# SCH__LM393_2022-09-28.net
KiCad netlist of a schematic drawn in EasyEDA
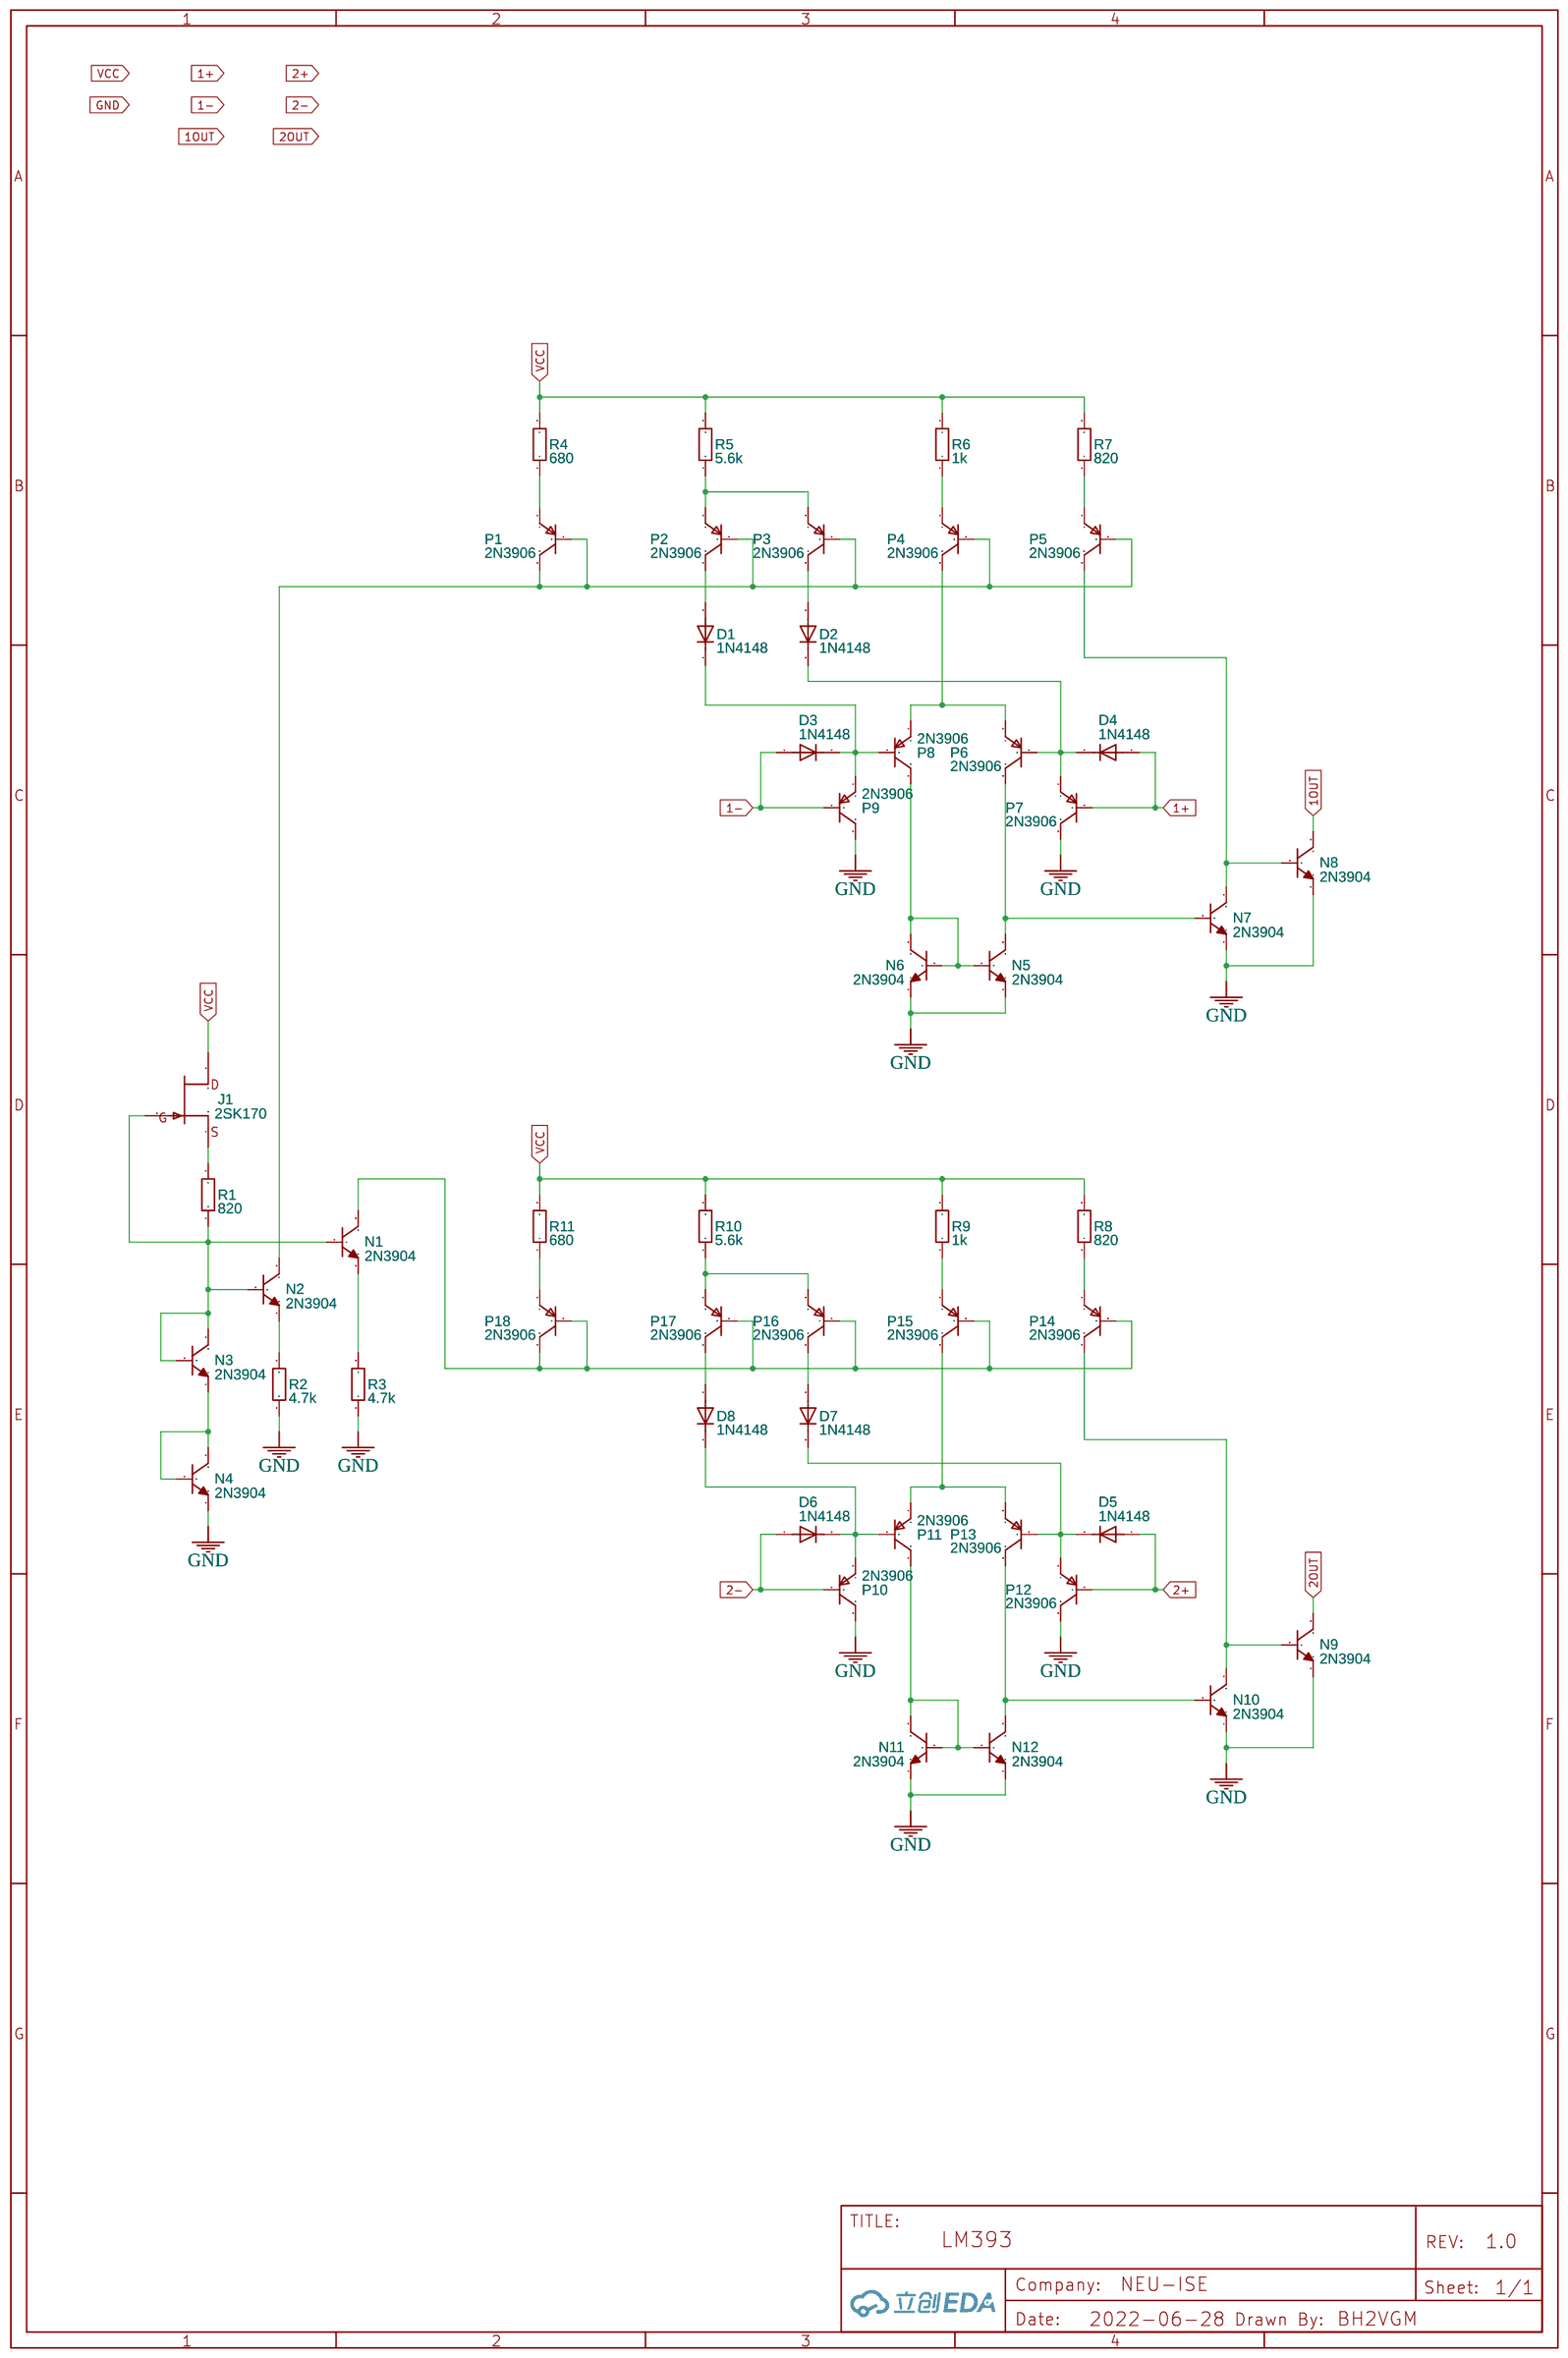
[diagram p0: schematic sheet]

(export (version "E")
  (design (tool "Eeschema 10.0.6"))
  (components
    (comp (ref "D1") (value "1N4148") (libsource (lib "") (part "1N4148 DO-35")))
    (comp (ref "D2") (value "1N4148") (libsource (lib "") (part "1N4148 DO-35")))
    (comp (ref "D3") (value "1N4148") (libsource (lib "") (part "1N4148 DO-35_1")))
    (comp (ref "D4") (value "1N4148") (libsource (lib "") (part "1N4148 DO-35_2")))
    (comp (ref "D5") (value "1N4148") (libsource (lib "") (part "1N4148 DO-35_2")))
    (comp (ref "D6") (value "1N4148") (libsource (lib "") (part "1N4148 DO-35_1")))
    (comp (ref "D7") (value "1N4148") (libsource (lib "") (part "1N4148 DO-35")))
    (comp (ref "D8") (value "1N4148") (libsource (lib "") (part "1N4148 DO-35")))
    (comp (ref "J1") (value "2SK170") (libsource (lib "") (part "2SK170")))
    (comp (ref "N1")
      (value "2N3904")
      (fields (field (name "BOM_Supplier Part") "C118538"))
      (libsource (lib "") (part "2N3904"))
    )
    (comp (ref "N2")
      (value "2N3904")
      (fields (field (name "BOM_Supplier Part") "C118538"))
      (libsource (lib "") (part "2N3904"))
    )
    (comp (ref "N3")
      (value "2N3904")
      (fields (field (name "BOM_Supplier Part") "C118538"))
      (libsource (lib "") (part "2N3904"))
    )
    (comp (ref "N4")
      (value "2N3904")
      (fields (field (name "BOM_Supplier Part") "C118538"))
      (libsource (lib "") (part "2N3904"))
    )
    (comp (ref "N5")
      (value "2N3904")
      (fields (field (name "BOM_Supplier Part") "C118538"))
      (libsource (lib "") (part "2N3904"))
    )
    (comp (ref "N6")
      (value "2N3904")
      (fields (field (name "BOM_Supplier Part") "C118538"))
      (libsource (lib "") (part "2N3904_1"))
    )
    (comp (ref "N7")
      (value "2N3904")
      (fields (field (name "BOM_Supplier Part") "C118538"))
      (libsource (lib "") (part "2N3904"))
    )
    (comp (ref "N8")
      (value "2N3904")
      (fields (field (name "BOM_Supplier Part") "C118538"))
      (libsource (lib "") (part "2N3904"))
    )
    (comp (ref "N9")
      (value "2N3904")
      (fields (field (name "BOM_Supplier Part") "C118538"))
      (libsource (lib "") (part "2N3904"))
    )
    (comp (ref "N10")
      (value "2N3904")
      (fields (field (name "BOM_Supplier Part") "C118538"))
      (libsource (lib "") (part "2N3904"))
    )
    (comp (ref "N11")
      (value "2N3904")
      (fields (field (name "BOM_Supplier Part") "C118538"))
      (libsource (lib "") (part "2N3904_1"))
    )
    (comp (ref "N12")
      (value "2N3904")
      (fields (field (name "BOM_Supplier Part") "C118538"))
      (libsource (lib "") (part "2N3904"))
    )
    (comp (ref "P1")
      (value "2N3906")
      (fields (field (name "BOM_Supplier Part") "C9809"))
      (libsource (lib "") (part "2N3906"))
    )
    (comp (ref "P2")
      (value "2N3906")
      (fields (field (name "BOM_Supplier Part") "C9809"))
      (libsource (lib "") (part "2N3906"))
    )
    (comp (ref "P3")
      (value "2N3906")
      (fields (field (name "BOM_Supplier Part") "C9809"))
      (libsource (lib "") (part "2N3906"))
    )
    (comp (ref "P4")
      (value "2N3906")
      (fields (field (name "BOM_Supplier Part") "C9809"))
      (libsource (lib "") (part "2N3906"))
    )
    (comp (ref "P5")
      (value "2N3906")
      (fields (field (name "BOM_Supplier Part") "C9809"))
      (libsource (lib "") (part "2N3906"))
    )
    (comp (ref "P6")
      (value "2N3906")
      (fields (field (name "BOM_Supplier Part") "C9809"))
      (libsource (lib "") (part "2N3906"))
    )
    (comp (ref "P7")
      (value "2N3906")
      (fields (field (name "BOM_Supplier Part") "C9809"))
      (libsource (lib "") (part "2N3906"))
    )
    (comp (ref "P8")
      (value "2N3906")
      (fields (field (name "BOM_Supplier Part") "C9809"))
      (libsource (lib "") (part "2N3906_1"))
    )
    (comp (ref "P9")
      (value "2N3906")
      (fields (field (name "BOM_Supplier Part") "C9809"))
      (libsource (lib "") (part "2N3906_1"))
    )
    (comp (ref "P10")
      (value "2N3906")
      (fields (field (name "BOM_Supplier Part") "C9809"))
      (libsource (lib "") (part "2N3906_1"))
    )
    (comp (ref "P11")
      (value "2N3906")
      (fields (field (name "BOM_Supplier Part") "C9809"))
      (libsource (lib "") (part "2N3906_1"))
    )
    (comp (ref "P12")
      (value "2N3906")
      (fields (field (name "BOM_Supplier Part") "C9809"))
      (libsource (lib "") (part "2N3906"))
    )
    (comp (ref "P13")
      (value "2N3906")
      (fields (field (name "BOM_Supplier Part") "C9809"))
      (libsource (lib "") (part "2N3906"))
    )
    (comp (ref "P14")
      (value "2N3906")
      (fields (field (name "BOM_Supplier Part") "C9809"))
      (libsource (lib "") (part "2N3906"))
    )
    (comp (ref "P15")
      (value "2N3906")
      (fields (field (name "BOM_Supplier Part") "C9809"))
      (libsource (lib "") (part "2N3906"))
    )
    (comp (ref "P16")
      (value "2N3906")
      (fields (field (name "BOM_Supplier Part") "C9809"))
      (libsource (lib "") (part "2N3906"))
    )
    (comp (ref "P17")
      (value "2N3906")
      (fields (field (name "BOM_Supplier Part") "C9809"))
      (libsource (lib "") (part "2N3906"))
    )
    (comp (ref "P18")
      (value "2N3906")
      (fields (field (name "BOM_Supplier Part") "C9809"))
      (libsource (lib "") (part "2N3906"))
    )
    (comp (ref "R1") (value "820") (libsource (lib "") (part "TR0805D220KP0550Z")))
    (comp (ref "R2") (value "4.7k") (libsource (lib "") (part "TR0805D220KP0550Z")))
    (comp (ref "R3") (value "4.7k") (libsource (lib "") (part "TR0805D220KP0550Z")))
    (comp (ref "R4") (value "680") (libsource (lib "") (part "TR0805D220KP0550Z")))
    (comp (ref "R5") (value "5.6k") (libsource (lib "") (part "TR0805D220KP0550Z")))
    (comp (ref "R6") (value "1k") (libsource (lib "") (part "TR0805D220KP0550Z")))
    (comp (ref "R7") (value "820") (libsource (lib "") (part "TR0805D220KP0550Z")))
    (comp (ref "R8") (value "820") (libsource (lib "") (part "TR0805D220KP0550Z")))
    (comp (ref "R9") (value "1k") (libsource (lib "") (part "TR0805D220KP0550Z")))
    (comp (ref "R10") (value "5.6k") (libsource (lib "") (part "TR0805D220KP0550Z")))
    (comp (ref "R11") (value "680") (libsource (lib "") (part "TR0805D220KP0550Z")))
  )
  (nets
    (net (code "1") (name "1+") (class "Default")
      (node (ref "D4") (pin "1") (pinfunction "1_1") (pintype "unspecified"))
      (node (ref "P7") (pin "2") (pinfunction "B_2") (pintype "unspecified"))
    )
    (net (code "2") (name "1-") (class "Default")
      (node (ref "D3") (pin "1") (pinfunction "1_1") (pintype "unspecified"))
      (node (ref "P9") (pin "2") (pinfunction "B_2") (pintype "unspecified"))
    )
    (net (code "3") (name "1OUT") (class "Default")
      (node (ref "N8") (pin "3") (pinfunction "C_3") (pintype "unspecified"))
    )
    (net (code "4") (name "2+") (class "Default")
      (node (ref "D5") (pin "1") (pinfunction "1_1") (pintype "unspecified"))
      (node (ref "P12") (pin "2") (pinfunction "B_2") (pintype "unspecified"))
    )
    (net (code "5") (name "2-") (class "Default")
      (node (ref "D6") (pin "1") (pinfunction "1_1") (pintype "unspecified"))
      (node (ref "P10") (pin "2") (pinfunction "B_2") (pintype "unspecified"))
    )
    (net (code "6") (name "2OUT") (class "Default")
      (node (ref "N9") (pin "3") (pinfunction "C_3") (pintype "unspecified"))
    )
    (net (code "7") (name "GND") (class "Default")
      (node (ref "N10") (pin "1") (pinfunction "E_1") (pintype "unspecified"))
      (node (ref "N11") (pin "1") (pinfunction "E_1") (pintype "unspecified"))
      (node (ref "N12") (pin "1") (pinfunction "E_1") (pintype "unspecified"))
      (node (ref "N4") (pin "1") (pinfunction "E_1") (pintype "unspecified"))
      (node (ref "N5") (pin "1") (pinfunction "E_1") (pintype "unspecified"))
      (node (ref "N6") (pin "1") (pinfunction "E_1") (pintype "unspecified"))
      (node (ref "N7") (pin "1") (pinfunction "E_1") (pintype "unspecified"))
      (node (ref "N8") (pin "1") (pinfunction "E_1") (pintype "unspecified"))
      (node (ref "N9") (pin "1") (pinfunction "E_1") (pintype "unspecified"))
      (node (ref "P10") (pin "3") (pinfunction "C_3") (pintype "unspecified"))
      (node (ref "P12") (pin "3") (pinfunction "C_3") (pintype "unspecified"))
      (node (ref "P7") (pin "3") (pinfunction "C_3") (pintype "unspecified"))
      (node (ref "P9") (pin "3") (pinfunction "C_3") (pintype "unspecified"))
      (node (ref "R2") (pin "1") (pinfunction "1_1") (pintype "input"))
      (node (ref "R3") (pin "1") (pinfunction "1_1") (pintype "input"))
    )
    (net (code "8") (name "Net-(J1-G)") (class "Default")
      (node (ref "J1") (pin "2") (pinfunction "G_2") (pintype "unspecified"))
      (node (ref "N1") (pin "2") (pinfunction "B_2") (pintype "unspecified"))
      (node (ref "N2") (pin "2") (pinfunction "B_2") (pintype "unspecified"))
      (node (ref "N3") (pin "2") (pinfunction "B_2") (pintype "unspecified"))
      (node (ref "N3") (pin "3") (pinfunction "C_3") (pintype "unspecified"))
      (node (ref "R1") (pin "1") (pinfunction "1_1") (pintype "input"))
    )
    (net (code "9") (name "Net-(J1-S)") (class "Default")
      (node (ref "J1") (pin "1") (pinfunction "S_1") (pintype "unspecified"))
      (node (ref "R1") (pin "2") (pinfunction "2_2") (pintype "input"))
    )
    (net (code "10") (name "Net-(N1-C)") (class "Default")
      (node (ref "N1") (pin "3") (pinfunction "C_3") (pintype "unspecified"))
      (node (ref "P14") (pin "2") (pinfunction "B_2") (pintype "unspecified"))
      (node (ref "P15") (pin "2") (pinfunction "B_2") (pintype "unspecified"))
      (node (ref "P16") (pin "2") (pinfunction "B_2") (pintype "unspecified"))
      (node (ref "P17") (pin "2") (pinfunction "B_2") (pintype "unspecified"))
      (node (ref "P18") (pin "2") (pinfunction "B_2") (pintype "unspecified"))
      (node (ref "P18") (pin "3") (pinfunction "C_3") (pintype "unspecified"))
    )
    (net (code "11") (name "Net-(N1-E)") (class "Default")
      (node (ref "N1") (pin "1") (pinfunction "E_1") (pintype "unspecified"))
      (node (ref "R3") (pin "2") (pinfunction "2_2") (pintype "input"))
    )
    (net (code "12") (name "Net-(N2-C)") (class "Default")
      (node (ref "N2") (pin "3") (pinfunction "C_3") (pintype "unspecified"))
      (node (ref "P1") (pin "2") (pinfunction "B_2") (pintype "unspecified"))
      (node (ref "P1") (pin "3") (pinfunction "C_3") (pintype "unspecified"))
      (node (ref "P2") (pin "2") (pinfunction "B_2") (pintype "unspecified"))
      (node (ref "P3") (pin "2") (pinfunction "B_2") (pintype "unspecified"))
      (node (ref "P4") (pin "2") (pinfunction "B_2") (pintype "unspecified"))
      (node (ref "P5") (pin "2") (pinfunction "B_2") (pintype "unspecified"))
    )
    (net (code "13") (name "Net-(N2-E)") (class "Default")
      (node (ref "N2") (pin "1") (pinfunction "E_1") (pintype "unspecified"))
      (node (ref "R2") (pin "2") (pinfunction "2_2") (pintype "input"))
    )
    (net (code "14") (name "Net-(N3-E)") (class "Default")
      (node (ref "N3") (pin "1") (pinfunction "E_1") (pintype "unspecified"))
      (node (ref "N4") (pin "2") (pinfunction "B_2") (pintype "unspecified"))
      (node (ref "N4") (pin "3") (pinfunction "C_3") (pintype "unspecified"))
    )
    (net (code "15") (name "Net-(N5-B)") (class "Default")
      (node (ref "N5") (pin "2") (pinfunction "B_2") (pintype "unspecified"))
      (node (ref "N6") (pin "2") (pinfunction "B_2") (pintype "unspecified"))
      (node (ref "N6") (pin "3") (pinfunction "C_3") (pintype "unspecified"))
      (node (ref "P8") (pin "3") (pinfunction "C_3") (pintype "unspecified"))
    )
    (net (code "16") (name "Net-(N5-C)") (class "Default")
      (node (ref "N5") (pin "3") (pinfunction "C_3") (pintype "unspecified"))
      (node (ref "N7") (pin "2") (pinfunction "B_2") (pintype "unspecified"))
      (node (ref "P6") (pin "3") (pinfunction "C_3") (pintype "unspecified"))
    )
    (net (code "17") (name "Net-(N7-C)") (class "Default")
      (node (ref "N7") (pin "3") (pinfunction "C_3") (pintype "unspecified"))
      (node (ref "N8") (pin "2") (pinfunction "B_2") (pintype "unspecified"))
      (node (ref "P5") (pin "3") (pinfunction "C_3") (pintype "unspecified"))
    )
    (net (code "18") (name "Net-(N10-B)") (class "Default")
      (node (ref "N10") (pin "2") (pinfunction "B_2") (pintype "unspecified"))
      (node (ref "N12") (pin "3") (pinfunction "C_3") (pintype "unspecified"))
      (node (ref "P13") (pin "3") (pinfunction "C_3") (pintype "unspecified"))
    )
    (net (code "19") (name "Net-(N10-C)") (class "Default")
      (node (ref "N10") (pin "3") (pinfunction "C_3") (pintype "unspecified"))
      (node (ref "N9") (pin "2") (pinfunction "B_2") (pintype "unspecified"))
      (node (ref "P14") (pin "3") (pinfunction "C_3") (pintype "unspecified"))
    )
    (net (code "20") (name "Net-(N11-B)") (class "Default")
      (node (ref "N11") (pin "2") (pinfunction "B_2") (pintype "unspecified"))
      (node (ref "N11") (pin "3") (pinfunction "C_3") (pintype "unspecified"))
      (node (ref "N12") (pin "2") (pinfunction "B_2") (pintype "unspecified"))
      (node (ref "P11") (pin "3") (pinfunction "C_3") (pintype "unspecified"))
    )
    (net (code "21") (name "Net-(P1-E)") (class "Default")
      (node (ref "P1") (pin "1") (pinfunction "E_1") (pintype "unspecified"))
      (node (ref "R4") (pin "1") (pinfunction "1_1") (pintype "input"))
    )
    (net (code "22") (name "Net-(P2-C)") (class "Default")
      (node (ref "D1") (pin "1") (pinfunction "1_1") (pintype "unspecified"))
      (node (ref "P2") (pin "3") (pinfunction "C_3") (pintype "unspecified"))
    )
    (net (code "23") (name "Net-(P2-E)") (class "Default")
      (node (ref "P2") (pin "1") (pinfunction "E_1") (pintype "unspecified"))
      (node (ref "P3") (pin "1") (pinfunction "E_1") (pintype "unspecified"))
      (node (ref "R5") (pin "1") (pinfunction "1_1") (pintype "input"))
    )
    (net (code "24") (name "Net-(P3-C)") (class "Default")
      (node (ref "D2") (pin "1") (pinfunction "1_1") (pintype "unspecified"))
      (node (ref "P3") (pin "3") (pinfunction "C_3") (pintype "unspecified"))
    )
    (net (code "25") (name "Net-(P4-C)") (class "Default")
      (node (ref "P4") (pin "3") (pinfunction "C_3") (pintype "unspecified"))
      (node (ref "P6") (pin "1") (pinfunction "E_1") (pintype "unspecified"))
      (node (ref "P8") (pin "1") (pinfunction "E_1") (pintype "unspecified"))
    )
    (net (code "26") (name "Net-(P4-E)") (class "Default")
      (node (ref "P4") (pin "1") (pinfunction "E_1") (pintype "unspecified"))
      (node (ref "R6") (pin "1") (pinfunction "1_1") (pintype "input"))
    )
    (net (code "27") (name "Net-(P5-E)") (class "Default")
      (node (ref "P5") (pin "1") (pinfunction "E_1") (pintype "unspecified"))
      (node (ref "R7") (pin "1") (pinfunction "1_1") (pintype "input"))
    )
    (net (code "28") (name "Net-(P6-B)") (class "Default")
      (node (ref "D2") (pin "2") (pinfunction "2_2") (pintype "unspecified"))
      (node (ref "D4") (pin "2") (pinfunction "2_2") (pintype "unspecified"))
      (node (ref "P6") (pin "2") (pinfunction "B_2") (pintype "unspecified"))
      (node (ref "P7") (pin "1") (pinfunction "E_1") (pintype "unspecified"))
    )
    (net (code "29") (name "Net-(P8-B)") (class "Default")
      (node (ref "D1") (pin "2") (pinfunction "2_2") (pintype "unspecified"))
      (node (ref "D3") (pin "2") (pinfunction "2_2") (pintype "unspecified"))
      (node (ref "P8") (pin "2") (pinfunction "B_2") (pintype "unspecified"))
      (node (ref "P9") (pin "1") (pinfunction "E_1") (pintype "unspecified"))
    )
    (net (code "30") (name "Net-(P10-E)") (class "Default")
      (node (ref "D6") (pin "2") (pinfunction "2_2") (pintype "unspecified"))
      (node (ref "D8") (pin "2") (pinfunction "2_2") (pintype "unspecified"))
      (node (ref "P10") (pin "1") (pinfunction "E_1") (pintype "unspecified"))
      (node (ref "P11") (pin "2") (pinfunction "B_2") (pintype "unspecified"))
    )
    (net (code "31") (name "Net-(P11-E)") (class "Default")
      (node (ref "P11") (pin "1") (pinfunction "E_1") (pintype "unspecified"))
      (node (ref "P13") (pin "1") (pinfunction "E_1") (pintype "unspecified"))
      (node (ref "P15") (pin "3") (pinfunction "C_3") (pintype "unspecified"))
    )
    (net (code "32") (name "Net-(P12-E)") (class "Default")
      (node (ref "D5") (pin "2") (pinfunction "2_2") (pintype "unspecified"))
      (node (ref "D7") (pin "2") (pinfunction "2_2") (pintype "unspecified"))
      (node (ref "P12") (pin "1") (pinfunction "E_1") (pintype "unspecified"))
      (node (ref "P13") (pin "2") (pinfunction "B_2") (pintype "unspecified"))
    )
    (net (code "33") (name "Net-(P14-E)") (class "Default")
      (node (ref "P14") (pin "1") (pinfunction "E_1") (pintype "unspecified"))
      (node (ref "R8") (pin "1") (pinfunction "1_1") (pintype "input"))
    )
    (net (code "34") (name "Net-(P15-E)") (class "Default")
      (node (ref "P15") (pin "1") (pinfunction "E_1") (pintype "unspecified"))
      (node (ref "R9") (pin "1") (pinfunction "1_1") (pintype "input"))
    )
    (net (code "35") (name "Net-(P16-C)") (class "Default")
      (node (ref "D7") (pin "1") (pinfunction "1_1") (pintype "unspecified"))
      (node (ref "P16") (pin "3") (pinfunction "C_3") (pintype "unspecified"))
    )
    (net (code "36") (name "Net-(P16-E)") (class "Default")
      (node (ref "P16") (pin "1") (pinfunction "E_1") (pintype "unspecified"))
      (node (ref "P17") (pin "1") (pinfunction "E_1") (pintype "unspecified"))
      (node (ref "R10") (pin "1") (pinfunction "1_1") (pintype "input"))
    )
    (net (code "37") (name "Net-(P17-C)") (class "Default")
      (node (ref "D8") (pin "1") (pinfunction "1_1") (pintype "unspecified"))
      (node (ref "P17") (pin "3") (pinfunction "C_3") (pintype "unspecified"))
    )
    (net (code "38") (name "Net-(P18-E)") (class "Default")
      (node (ref "P18") (pin "1") (pinfunction "E_1") (pintype "unspecified"))
      (node (ref "R11") (pin "1") (pinfunction "1_1") (pintype "input"))
    )
    (net (code "39") (name "VCC") (class "Default")
      (node (ref "J1") (pin "3") (pinfunction "D_3") (pintype "unspecified"))
      (node (ref "R10") (pin "2") (pinfunction "2_2") (pintype "input"))
      (node (ref "R11") (pin "2") (pinfunction "2_2") (pintype "input"))
      (node (ref "R4") (pin "2") (pinfunction "2_2") (pintype "input"))
      (node (ref "R5") (pin "2") (pinfunction "2_2") (pintype "input"))
      (node (ref "R6") (pin "2") (pinfunction "2_2") (pintype "input"))
      (node (ref "R7") (pin "2") (pinfunction "2_2") (pintype "input"))
      (node (ref "R8") (pin "2") (pinfunction "2_2") (pintype "input"))
      (node (ref "R9") (pin "2") (pinfunction "2_2") (pintype "input"))
    )
  )
)
